# BUCKEDUP.net
KiCad netlist of a schematic drawn in Altium Designer
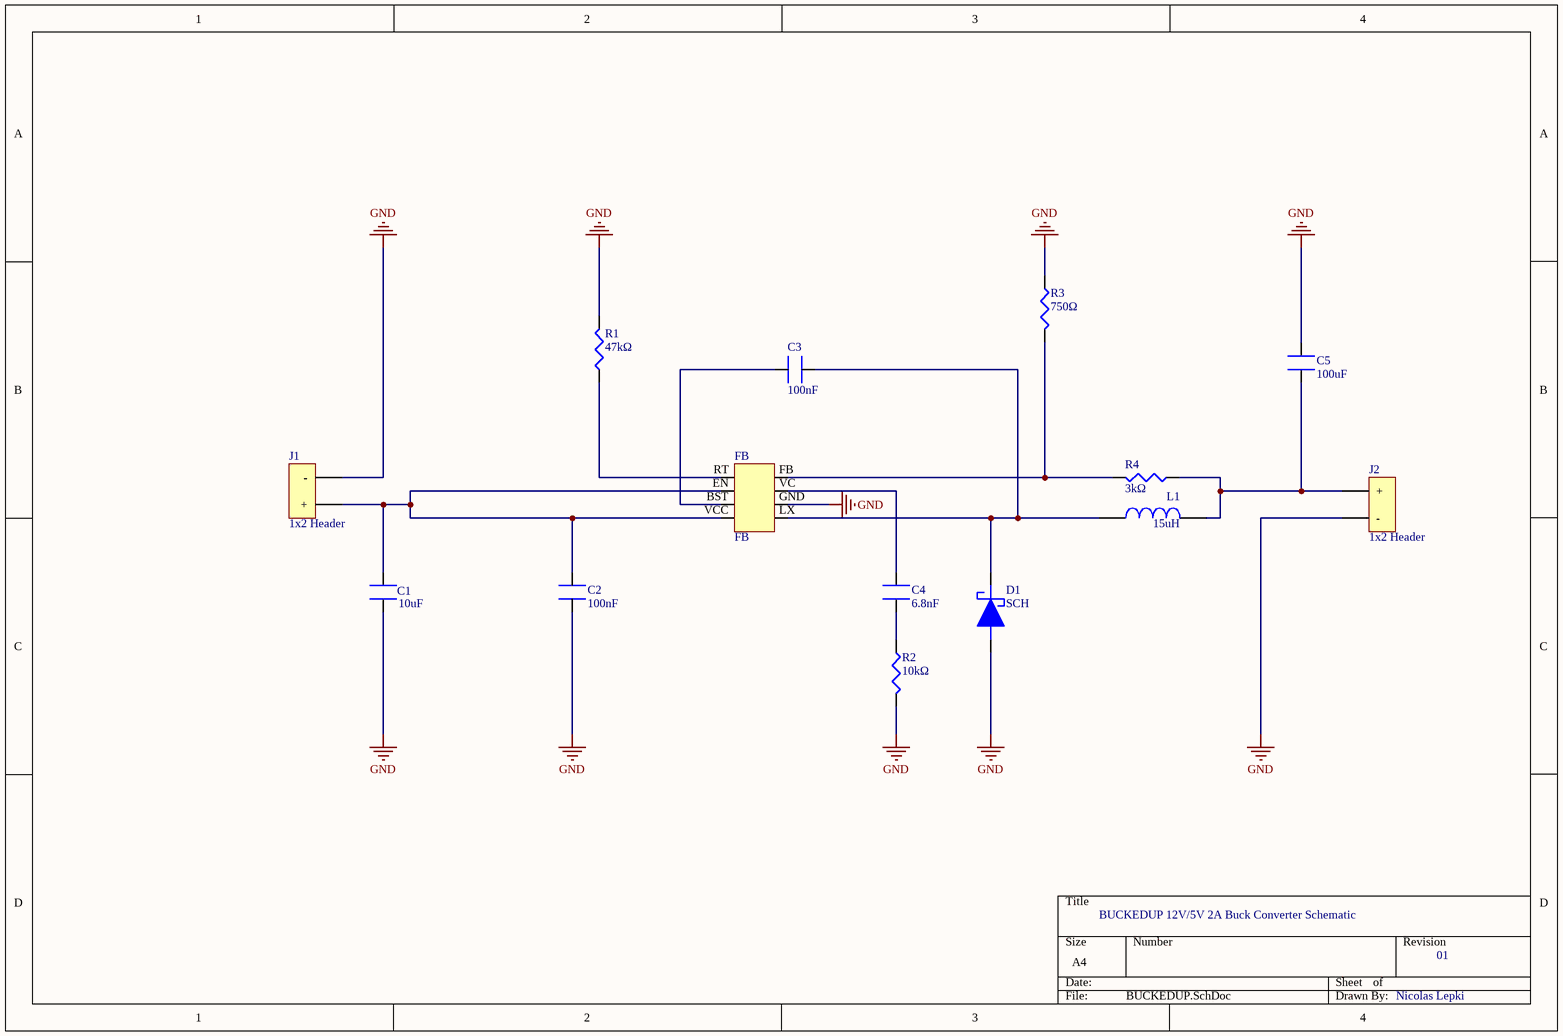
[diagram p0: BUCKEDUP.SchDoc]

(export (version "E")
  (design (tool "Eeschema 10.0.6"))
  (components
    (comp (ref "C1")
      (value "10uF")
      (fields
        (field (name "MANUFACTURER") "KYOCERA AVX")
        (field (name "MANUFACTURER PART NUMBER") "KAM32LR71H106KL")
      )
      (libsource (lib "BUCKEDUP_SchLib") (part "KAM32LR71H106KL"))
    )
    (comp (ref "C2")
      (value "100nF")
      (fields
        (field (name "MANUFACTURER") "Samsung Electro-Mechanics")
        (field (name "MANUFACTURER PART NUMBER") "CL10F104ZB8NNNC")
        (field (name "TOLERANCE") "80%")
      )
      (libsource (lib "BUCKEDUP_SchLib") (part "CL10F104ZB8NNNC"))
    )
    (comp (ref "C3")
      (value "100nF")
      (fields
        (field (name "MANUFACTURER") "Samsung Electro-Mechanics")
        (field (name "MANUFACTURER PART NUMBER") "CL10F104ZB8NNNC")
        (field (name "TOLERANCE") "80%")
      )
      (libsource (lib "BUCKEDUP_SchLib") (part "CL10F104ZB8NNNC"))
    )
    (comp (ref "C4")
      (value "6.8nF")
      (fields
        (field (name "MANUFACTURER") "Yageo Group")
        (field (name "MANUFACTURER PART NUMBER") "CC0402JRX7R9BB682")
        (field (name "TOLERANCE") "5%")
      )
      (libsource (lib "BUCKEDUP_SchLib") (part "CC0402JRX7R9BB682"))
    )
    (comp (ref "C5")
      (value "100uF")
      (description "100uF 1210 16 V ±20% Tolerance X5R SMT Multilayer Ceramic Capacitor")
      (fields
        (field (name "MANUFACTURER") "Taiyo Yuden")
        (field (name "MANUFACTURER PART NUMBER") "EMK325ABJ107MM-T")
      )
      (libsource (lib "BUCKEDUP_SchLib") (part "EMK325ABJ107MM-T"))
    )
    (comp (ref "D1")
      (value "SCH")
      (description "Rectifier Diode, Schottky, 1 Phase, 1 Element, 3A, 100V V(RRM), Silicon")
      (fields (field (name "MANUFACTURER") "ROHM") (field (name "MANUFACTURER PART NUMBER") "YQ3VWM10BTR"))
      (libsource (lib "BUCKEDUP_SchLib") (part "YQ3VWM10BTR"))
    )
    (comp (ref "FB")
      (value "FB")
      (description "DC/DC Buck Regulator, Adjustable, 12V to 76V In, 1V to 76V/3A Out, 750kHz, HTSOP-8")
      (fields
        (field (name "MANUFACTURER") "ROHM")
        (field (name "MANUFACTURER PART NUMBER") "BD9G341AEFJ-LBE2")
      )
      (libsource (lib "BUCKEDUP_SchLib") (part "BD9G341AEFJ-LBE2"))
    )
    (comp (ref "J1")
      (value "1x2 Header")
      (description "Screw Terminals 5MM Pitch (2-PIN")
      (fields (field (name "MANUFACTURER") "SparkFun") (field (name "MANUFACTURER PART NUMBER") "08432"))
      (libsource (lib "BUCKEDUP_SchLib") (part "08432"))
    )
    (comp (ref "J2")
      (value "1x2 Header")
      (description "Screw Terminals 5MM Pitch (2-PIN")
      (fields (field (name "MANUFACTURER") "SparkFun") (field (name "MANUFACTURER PART NUMBER") "08432"))
      (libsource (lib "") (part "08432_1"))
    )
    (comp (ref "L1")
      (value "15uH")
      (description "15uH PA4343 Power Inductor, up to 55A, 6.5mm Max Height")
      (fields
        (field (name "MANUFACTURER") "Pulse Electronics")
        (field (name "MANUFACTURER PART NUMBER") "PM4343.153NLT")
      )
      (libsource (lib "BUCKEDUP_SchLib") (part "PM4343.153NLT"))
    )
    (comp (ref "R1")
      (value "47kΩ")
      (description "47kΩ Res Thick Film 0603 47K Ohm 1% 1/10W ±100ppm/°C Molded SMD Paper T/R")
      (fields
        (field (name "MANUFACTURER") "Yageo Group")
        (field (name "MANUFACTURER PART NUMBER") "RC0603FR-0747KL")
      )
      (libsource (lib "BUCKEDUP_SchLib") (part "RC0603FR-0747KL"))
    )
    (comp (ref "R2")
      (value "10kΩ")
      (description "10kΩ 100Mw Thick Film Resistors 100Ppm/ 1% 10K 0603 Chip Resistor Surface Mount Rohs")
      (fields
        (field (name "MANUFACTURER") "Yageo Group")
        (field (name "MANUFACTURER PART NUMBER") "RC0603FR-07100KL")
      )
      (libsource (lib "BUCKEDUP_SchLib") (part "RC0603FR-07100KL"))
    )
    (comp (ref "R3")
      (value "750Ω")
      (description "750Ω Resistor Thick Film 0603 750 Ohm 1% 1/10W 100ppm/C Molded SMD Punched Carrier T/R")
      (fields
        (field (name "MANUFACTURER") "Panasonic")
        (field (name "MANUFACTURER PART NUMBER") "ERJ-3EKF75R0V")
      )
      (libsource (lib "BUCKEDUP_SchLib") (part "ERJ-3EKF75R0V"))
    )
    (comp (ref "R4")
      (value "3kΩ")
      (description "3kΩ Res Thick Film 0603 3K Ohm 1% 0.1W(1/10W) ±100ppm/C Pad SMD Automotive T/R")
      (fields
        (field (name "MANUFACTURER") "Stackpole Electronics")
        (field (name "MANUFACTURER PART NUMBER") "RMCF0603FT3K00")
      )
      (libsource (lib "BUCKEDUP_SchLib") (part "RMCF0603FT3K00"))
    )
  )
  (nets
    (net (code "1") (name "GND") (class "Default")
      (node (ref "C1") (pin "2") (pinfunction "2_2") (pintype "passive"))
      (node (ref "C2") (pin "2") (pinfunction "2_2") (pintype "passive"))
      (node (ref "C5") (pin "2") (pinfunction "2_2") (pintype "passive"))
      (node (ref "D1") (pin "1") (pinfunction "1_1") (pintype "passive"))
      (node (ref "FB") (pin "GND") (pinfunction "*_GND") (pintype "passive"))
      (node (ref "J1") (pin "2") (pinfunction "-_2") (pintype "passive"))
      (node (ref "J2") (pin "2") (pinfunction "-_2") (pintype "passive"))
      (node (ref "R1") (pin "2") (pinfunction "2_2") (pintype "passive"))
      (node (ref "R2") (pin "2") (pinfunction "2_2") (pintype "passive"))
      (node (ref "R3") (pin "1") (pinfunction "1_1") (pintype "passive"))
    )
    (net (code "2") (name "Net-(C3-Pad1)") (class "Default")
      (node (ref "C3") (pin "1") (pinfunction "1_1") (pintype "passive"))
      (node (ref "FB") (pin "BST") (pinfunction "*_BST") (pintype "passive"))
    )
    (net (code "3") (name "Net-(C3-Pad2)") (class "Default")
      (node (ref "C3") (pin "2") (pinfunction "2_2") (pintype "passive"))
      (node (ref "D1") (pin "2") (pinfunction "2_2") (pintype "passive"))
      (node (ref "FB") (pin "LX") (pinfunction "*_LX") (pintype "passive"))
      (node (ref "L1") (pin "1") (pinfunction "1_1") (pintype "passive"))
    )
    (net (code "4") (name "Net-(C4-Pad1)") (class "Default")
      (node (ref "C4") (pin "1") (pinfunction "1_1") (pintype "passive"))
      (node (ref "FB") (pin "VC") (pinfunction "*_VC") (pintype "passive"))
    )
    (net (code "5") (name "Net-(C4-Pad2)") (class "Default")
      (node (ref "C4") (pin "2") (pinfunction "2_2") (pintype "passive"))
      (node (ref "R2") (pin "1") (pinfunction "1_1") (pintype "passive"))
    )
    (net (code "6") (name "Net-(FB-*-PadFB)") (class "Default")
      (node (ref "FB") (pin "FB") (pinfunction "*_FB") (pintype "passive"))
      (node (ref "R3") (pin "2") (pinfunction "2_2") (pintype "passive"))
      (node (ref "R4") (pin "2") (pinfunction "2_2") (pintype "passive"))
    )
    (net (code "7") (name "Net-(FB-*-PadRT)") (class "Default")
      (node (ref "FB") (pin "RT") (pinfunction "*_RT") (pintype "passive"))
      (node (ref "R1") (pin "1") (pinfunction "1_1") (pintype "passive"))
    )
    (net (code "8") (name "Net-(J1-+)") (class "Default")
      (node (ref "C1") (pin "1") (pinfunction "1_1") (pintype "passive"))
      (node (ref "C2") (pin "1") (pinfunction "1_1") (pintype "passive"))
      (node (ref "FB") (pin "EN") (pinfunction "*_EN") (pintype "passive"))
      (node (ref "FB") (pin "VCC") (pinfunction "*_VCC") (pintype "passive"))
      (node (ref "J1") (pin "1") (pinfunction "+_1") (pintype "passive"))
    )
    (net (code "9") (name "Net-(J2-+)") (class "Default")
      (node (ref "C5") (pin "1") (pinfunction "1_1") (pintype "passive"))
      (node (ref "J2") (pin "1") (pinfunction "+_1") (pintype "passive"))
      (node (ref "L1") (pin "2") (pinfunction "2_2") (pintype "passive"))
      (node (ref "R4") (pin "1") (pinfunction "1_1") (pintype "passive"))
    )
  )
)
